# DEP_REVC.net
KiCad netlist of a schematic drawn in Altium Designer
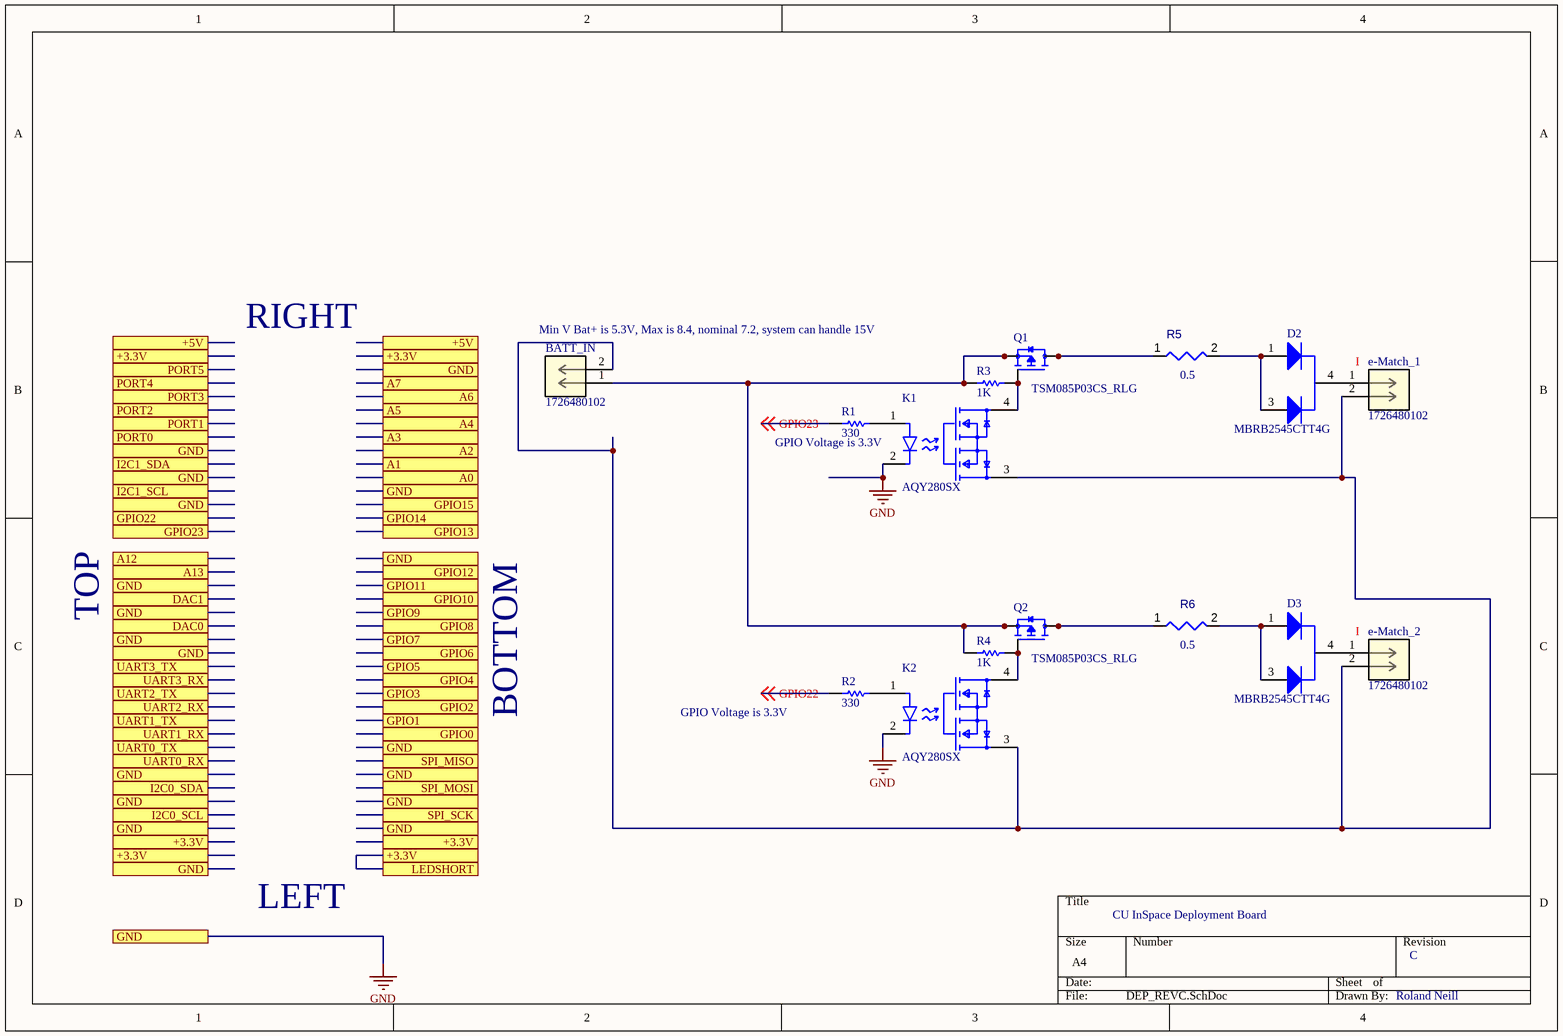
[diagram p0: DEP_REVC.SchDoc]

(export (version "E")
  (design (tool "Eeschema 10.0.6"))
  (components
    (comp (ref "BATT_IN")
      (value "1726480102")
      (footprint "CON_1726480102")
      (description "No Description Available")
      (fields (field (name "COPYRIGHT") "Copyright (C) 2022 Ultra Librarian. All rights reserved."))
      (libsource (lib "1726480102") (part "1726480102"))
    )
    (comp (ref "D2")
      (value "MBRB2545CTT4G")
      (footprint "ONSC-D2PAK-3-418B-04_V")
      (description "Rectifier Diode Schottky 45V 30A 3-Pin(2+Tab) D2PAK T/R")
      (libsource (lib "Americas- CU InSpace-  Carleton University") (part "ONSC-D-A1A3K4-3_B"))
    )
    (comp (ref "D3")
      (value "MBRB2545CTT4G")
      (footprint "ONSC-D2PAK-3-418B-04_V")
      (description "Rectifier Diode Schottky 45V 30A 3-Pin(2+Tab) D2PAK T/R")
      (libsource (lib "Americas- CU InSpace-  Carleton University") (part "ONSC-D-A1A3K4-3_B"))
    )
    (comp (ref "e-Match_1")
      (value "1726480102")
      (footprint "CON_1726480102")
      (description "No Description Available")
      (fields (field (name "COPYRIGHT") "Copyright (C) 2022 Ultra Librarian. All rights reserved."))
      (libsource (lib "DEP_REVC") (part "1726480102"))
    )
    (comp (ref "e-Match_2")
      (value "1726480102")
      (footprint "CON_1726480102")
      (description "No Description Available")
      (fields (field (name "COPYRIGHT") "Copyright (C) 2022 Ultra Librarian. All rights reserved."))
      (libsource (lib "DEP_REVC") (part "1726480102"))
    )
    (comp (ref "K1")
      (value "AQY280SX")
      (footprint "FP-AQY282SZ-IPC_A")
      (description "Relay Ssr 50MA 1.5V Dc-in 0.5A 60V Ac/dc-out 4-PIN Sop T/r")
      (libsource (lib "Americas- CU InSpace-  Carleton University") (part "9a6b4e52c44014f522c27d999989041"))
    )
    (comp (ref "K2")
      (value "AQY280SX")
      (footprint "FP-AQY282SZ-IPC_A")
      (description "Relay Ssr 50MA 1.5V Dc-in 0.5A 60V Ac/dc-out 4-PIN Sop T/r")
      (libsource (lib "Americas- CU InSpace-  Carleton University") (part "9a6b4e52c44014f522c27d999989041"))
    )
    (comp (ref "Q1")
      (value "TSM085P03CS_RLG")
      (footprint "SOP127P600X200-8N")
      (fields (field (name "MF") "{'manufacturer': u'Taiwan Semiconductor'}"))
      (libsource (lib "SnapEDA_Library") (part "TSM085P03CS_RLG"))
    )
    (comp (ref "Q2")
      (value "TSM085P03CS_RLG")
      (footprint "SOP127P600X200-8N")
      (fields (field (name "MF") "{'manufacturer': u'Taiwan Semiconductor'}"))
      (libsource (lib "SnapEDA_Library") (part "TSM085P03CS_RLG"))
    )
    (comp (ref "R1")
      (value "330")
      (footprint "6-0805_N")
      (description "Resistor")
      (libsource (lib "Simulation Generic Components") (part "Resistor"))
    )
    (comp (ref "R2")
      (value "330")
      (footprint "6-0805_N")
      (description "Resistor")
      (libsource (lib "Simulation Generic Components") (part "Resistor"))
    )
    (comp (ref "R3")
      (value "1K")
      (footprint "6-0805_N")
      (description "Resistor")
      (libsource (lib "Simulation Generic Components") (part "Resistor"))
    )
    (comp (ref "R4")
      (value "1K")
      (footprint "6-0805_N")
      (description "Resistor")
      (libsource (lib "Simulation Generic Components") (part "Resistor"))
    )
    (comp (ref "R5")
      (value "35221R5JT")
      (footprint "RESC6432X12N")
      (description "Res Thick Film 2512 1.5 Ohm 5% 3W ±200ppm/°C Molded SMD T/R")
      (fields (field (name "RESISTANCE") "0.5"))
      (libsource (lib "Americas- CU InSpace-  Carleton University") (part "RES-2"))
    )
    (comp (ref "R6")
      (value "35221R5JT")
      (footprint "RESC6432X12N")
      (description "Res Thick Film 2512 1.5 Ohm 5% 3W ±200ppm/°C Molded SMD T/R")
      (fields (field (name "RESISTANCE") "0.5"))
      (libsource (lib "Americas- CU InSpace-  Carleton University") (part "RES-2"))
    )
  )
  (nets
    (net (code "52") (name "GND") (class "Default")
      (node (ref "K1") (pin "2") (pinfunction "DC-_2") (pintype "passive"))
      (node (ref "K2") (pin "2") (pinfunction "DC-_2") (pintype "passive"))
    )
    (net (code "53") (name "GPIO22") (class "Default")
      (node (ref "R2") (pin "1") (pinfunction "1_1") (pintype "passive"))
    )
    (net (code "54") (name "GPIO23") (class "Default")
      (node (ref "R1") (pin "1") (pinfunction "1_1") (pintype "passive"))
    )
    (net (code "55") (name "Net-(BATT_IN-Pad1)") (class "Default")
      (node (ref "BATT_IN") (pin "1") (pinfunction "1_1") (pintype "passive"))
      (node (ref "Q1") (pin "1") (pinfunction "S_1") (pintype "passive"))
      (node (ref "Q1") (pin "2") (pinfunction "S_2") (pintype "passive"))
      (node (ref "Q1") (pin "3") (pinfunction "S_3") (pintype "passive"))
      (node (ref "Q2") (pin "1") (pinfunction "S_1") (pintype "passive"))
      (node (ref "Q2") (pin "2") (pinfunction "S_2") (pintype "passive"))
      (node (ref "Q2") (pin "3") (pinfunction "S_3") (pintype "passive"))
      (node (ref "R3") (pin "1") (pinfunction "1_1") (pintype "passive"))
      (node (ref "R4") (pin "1") (pinfunction "1_1") (pintype "passive"))
    )
    (net (code "56") (name "Net-(D2-A1)") (class "Default")
      (node (ref "D2") (pin "1") (pinfunction "A1_1") (pintype "passive"))
      (node (ref "D2") (pin "3") (pinfunction "A2_3") (pintype "passive"))
      (node (ref "R5") (pin "2") (pinfunction "2_2") (pintype "passive"))
    )
    (net (code "57") (name "Net-(D2-K)") (class "Default")
      (node (ref "D2") (pin "4") (pinfunction "K_4") (pintype "passive"))
      (node (ref "e-Match_1") (pin "1") (pinfunction "1_1") (pintype "passive"))
    )
    (net (code "58") (name "Net-(D3-A1)") (class "Default")
      (node (ref "D3") (pin "1") (pinfunction "A1_1") (pintype "passive"))
      (node (ref "D3") (pin "3") (pinfunction "A2_3") (pintype "passive"))
      (node (ref "R6") (pin "2") (pinfunction "2_2") (pintype "passive"))
    )
    (net (code "59") (name "Net-(D3-K)") (class "Default")
      (node (ref "D3") (pin "4") (pinfunction "K_4") (pintype "passive"))
      (node (ref "e-Match_2") (pin "1") (pinfunction "1_1") (pintype "passive"))
    )
    (net (code "60") (name "Net-(K1-1_AC{slash}DC)") (class "Default")
      (node (ref "BATT_IN") (pin "2") (pinfunction "2_2") (pintype "passive"))
      (node (ref "K1") (pin "3") (pinfunction "1_AC/DC_3") (pintype "passive"))
      (node (ref "K2") (pin "3") (pinfunction "1_AC/DC_3") (pintype "passive"))
      (node (ref "e-Match_1") (pin "2") (pinfunction "2_2") (pintype "passive"))
      (node (ref "e-Match_2") (pin "2") (pinfunction "2_2") (pintype "passive"))
    )
    (net (code "61") (name "Net-(K1-2_AC{slash}DC)") (class "Default")
      (node (ref "K1") (pin "4") (pinfunction "2_AC/DC_4") (pintype "passive"))
      (node (ref "Q1") (pin "4") (pinfunction "G_4") (pintype "passive"))
      (node (ref "R3") (pin "2") (pinfunction "2_2") (pintype "passive"))
    )
    (net (code "62") (name "Net-(K1-DC+)") (class "Default")
      (node (ref "K1") (pin "1") (pinfunction "DC+_1") (pintype "passive"))
      (node (ref "R1") (pin "2") (pinfunction "2_2") (pintype "passive"))
    )
    (net (code "63") (name "Net-(K2-2_AC{slash}DC)") (class "Default")
      (node (ref "K2") (pin "4") (pinfunction "2_AC/DC_4") (pintype "passive"))
      (node (ref "Q2") (pin "4") (pinfunction "G_4") (pintype "passive"))
      (node (ref "R4") (pin "2") (pinfunction "2_2") (pintype "passive"))
    )
    (net (code "64") (name "Net-(K2-DC+)") (class "Default")
      (node (ref "K2") (pin "1") (pinfunction "DC+_1") (pintype "passive"))
      (node (ref "R2") (pin "2") (pinfunction "2_2") (pintype "passive"))
    )
    (net (code "65") (name "Net-(Q1-D-Pad5)") (class "Default")
      (node (ref "Q1") (pin "5") (pinfunction "D_5") (pintype "passive"))
      (node (ref "Q1") (pin "6") (pinfunction "D_6") (pintype "passive"))
      (node (ref "Q1") (pin "7") (pinfunction "D_7") (pintype "passive"))
      (node (ref "Q1") (pin "8") (pinfunction "D_8") (pintype "passive"))
      (node (ref "R5") (pin "1") (pinfunction "1_1") (pintype "passive"))
    )
    (net (code "66") (name "Net-(Q2-D-Pad5)") (class "Default")
      (node (ref "Q2") (pin "5") (pinfunction "D_5") (pintype "passive"))
      (node (ref "Q2") (pin "6") (pinfunction "D_6") (pintype "passive"))
      (node (ref "Q2") (pin "7") (pinfunction "D_7") (pintype "passive"))
      (node (ref "Q2") (pin "8") (pinfunction "D_8") (pintype "passive"))
      (node (ref "R6") (pin "1") (pinfunction "1_1") (pintype "passive"))
    )
  )
)
